# PIC18F2550-USB-HID-LC-Meter.net
KiCad netlist of a schematic drawn in EAGLE
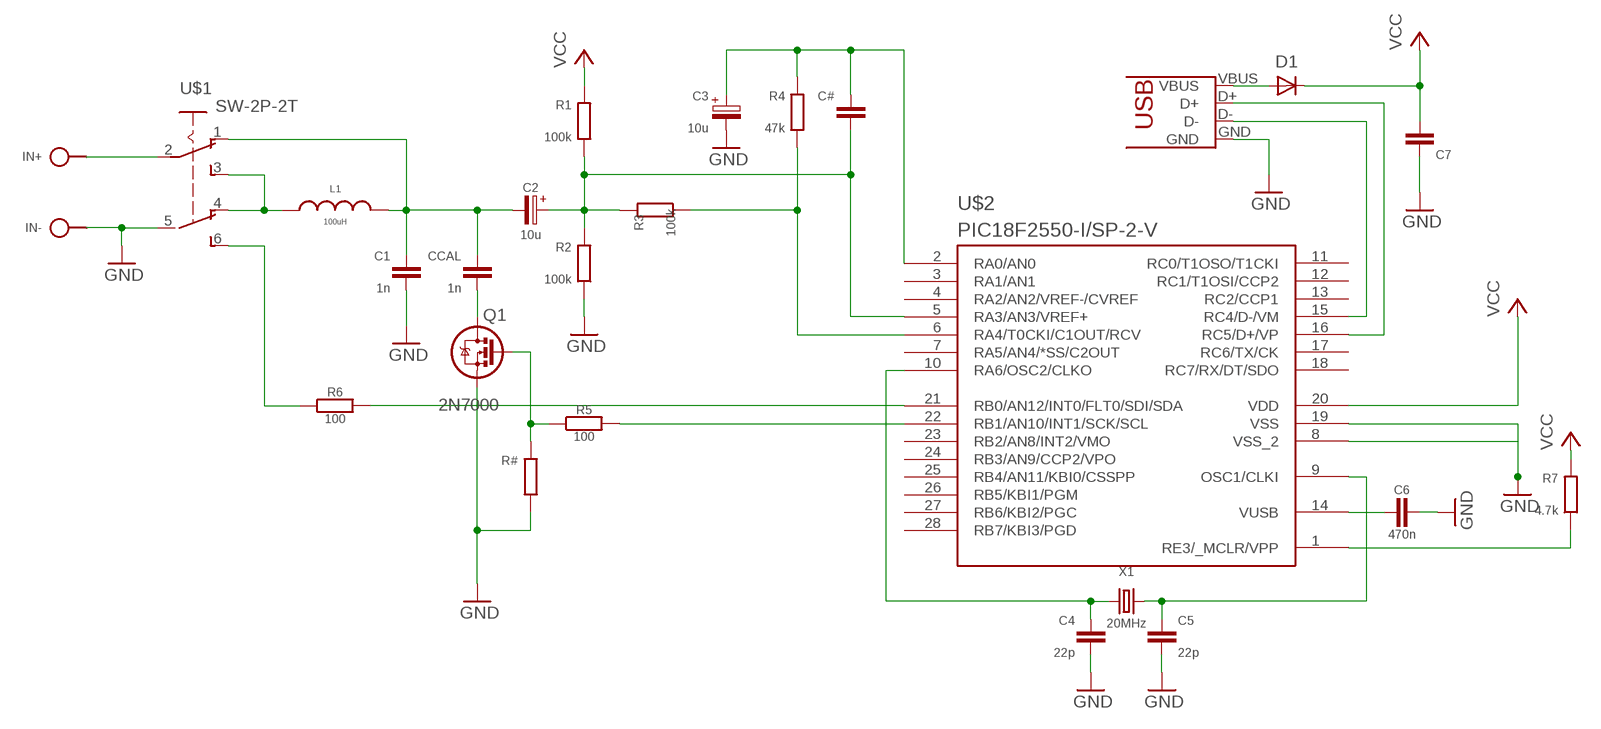
[diagram p0: schematic, sheet 1]

(export (version "E")
  (design (tool "Eeschema 10.0.6"))
  (components
    (comp (ref "C#")
      (value "C050-020X036")
      (footprint "eagle-import:C050-020X036")
      (libsource (lib "eagle-import") (part "C050-020X036"))
    )
    (comp (ref "C1")
      (value "1n")
      (footprint "eagle-import:C050-020X036")
      (libsource (lib "eagle-import") (part "C050-020X036"))
    )
    (comp (ref "C2")
      (value "10u")
      (footprint "eagle-import:E2.5-4_V")
      (libsource (lib "eagle-import") (part "CPOLE2,5-4/V"))
    )
    (comp (ref "C3")
      (value "10u")
      (footprint "eagle-import:E2,5-4")
      (libsource (lib "eagle-import") (part "CPOLE2,5-4"))
    )
    (comp (ref "C4")
      (value "22p")
      (footprint "eagle-import:C025-015X024_V")
      (libsource (lib "eagle-import") (part "C025-015X024"))
    )
    (comp (ref "C5")
      (value "22p")
      (footprint "eagle-import:C025-015X024_V")
      (libsource (lib "eagle-import") (part "C025-015X024"))
    )
    (comp (ref "C6")
      (value "470n")
      (footprint "eagle-import:C050-020X036")
      (libsource (lib "eagle-import") (part "C050-020X036"))
    )
    (comp (ref "C7")
      (value "C050-020X036")
      (footprint "eagle-import:C050-020X036")
      (libsource (lib "eagle-import") (part "C050-020X036"))
    )
    (comp (ref "CCAL")
      (value "1n")
      (footprint "eagle-import:C050-020X036")
      (libsource (lib "eagle-import") (part "C050-020X036"))
    )
    (comp (ref "D1")
      (value "1N414834-5")
      (footprint "eagle-import:DO34-5")
      (libsource (lib "eagle-import") (part "1N414834-5"))
    )
    (comp (ref "IN+")
      (value "SPAD")
      (footprint "eagle-import:SPAD")
      (libsource (lib "eagle-import") (part "SPAD"))
    )
    (comp (ref "IN-")
      (value "SPAD")
      (footprint "eagle-import:SPAD")
      (libsource (lib "eagle-import") (part "SPAD"))
    )
    (comp (ref "J1")
      (value "USB-PRINT")
      (footprint "eagle-import:USB-B-PRINT")
      (libsource (lib "eagle-import") (part "USB-PRINT"))
    )
    (comp (ref "L1")
      (value "100uH")
      (footprint "eagle-import:L-04_10-M")
      (libsource (lib "eagle-import") (part "L04/7-M"))
    )
    (comp (ref "Q1")
      (value "2N7000")
      (footprint "eagle-import:TO92")
      (libsource (lib "eagle-import") (part "2N7000"))
    )
    (comp (ref "R#")
      (value "R0202/7")
      (footprint "eagle-import:0202_7")
      (libsource (lib "eagle-import") (part "R0202/7"))
    )
    (comp (ref "R1")
      (value "100k")
      (footprint "eagle-import:0202_7")
      (libsource (lib "eagle-import") (part "R0202/7"))
    )
    (comp (ref "R2")
      (value "100k")
      (footprint "eagle-import:0202_7")
      (libsource (lib "eagle-import") (part "R0202/7"))
    )
    (comp (ref "R3")
      (value "100k")
      (footprint "eagle-import:0202_7")
      (libsource (lib "eagle-import") (part "R0202/7"))
    )
    (comp (ref "R4")
      (value "47k")
      (footprint "eagle-import:0202_7")
      (libsource (lib "eagle-import") (part "R0202/7"))
    )
    (comp (ref "R5")
      (value "100")
      (footprint "eagle-import:0202_7")
      (libsource (lib "eagle-import") (part "R0202/7"))
    )
    (comp (ref "R6")
      (value "100")
      (footprint "eagle-import:0202_7")
      (libsource (lib "eagle-import") (part "R0202/7"))
    )
    (comp (ref "R7")
      (value "4.7k")
      (footprint "eagle-import:0202_7")
      (libsource (lib "eagle-import") (part "R0202/7"))
    )
    (comp (ref "U$1")
      (value "SW-2P-2T")
      (footprint "eagle-import:SLSW-2P2T")
      (libsource (lib "eagle-import") (part "SW-2P-2T"))
    )
    (comp (ref "U$2")
      (value "PIC18F2550-I/SP-2-V")
      (footprint "eagle-import:DIL28-3_V")
      (libsource (lib "eagle-import") (part "PIC18F2550-I/SP-2-V"))
    )
    (comp (ref "X1")
      (value "20MHz")
      (footprint "eagle-import:HC49")
      (libsource (lib "eagle-import") (part "CRYSTALHC49"))
    )
  )
  (nets
    (net (code "1") (name "GND") (class "Default")
      (node (ref "C1") (pin "2") (pinfunction "2_2") (pintype "passive"))
      (node (ref "C3") (pin "-") (pinfunction "-_-") (pintype "passive"))
      (node (ref "C4") (pin "2") (pinfunction "2_2") (pintype "passive"))
      (node (ref "C5") (pin "2") (pinfunction "2_2") (pintype "passive"))
      (node (ref "C6") (pin "2") (pinfunction "2_2") (pintype "passive"))
      (node (ref "C7") (pin "1") (pinfunction "1_1") (pintype "passive"))
      (node (ref "IN-") (pin "1") (pinfunction "P$1_1") (pintype "bidirectional"))
      (node (ref "J1") (pin "GND") (pinfunction "GND_GND") (pintype "bidirectional"))
      (node (ref "Q1") (pin "1") (pinfunction "S_1") (pintype "passive"))
      (node (ref "R#") (pin "1") (pinfunction "1_1") (pintype "passive"))
      (node (ref "R2") (pin "1") (pinfunction "1_1") (pintype "passive"))
      (node (ref "U$1") (pin "5") (pinfunction "P1_5") (pintype "passive"))
      (node (ref "U$2") (pin "19") (pinfunction "VSS_19") (pintype "passive"))
      (node (ref "U$2") (pin "8") (pinfunction "VSS_2_8") (pintype "passive"))
    )
    (net (code "2") (name "Net-(D1-PadA)") (class "Default")
      (node (ref "D1") (pin "A") (pinfunction "A_A") (pintype "passive"))
      (node (ref "J1") (pin "VBUS") (pinfunction "VBUS_VBUS") (pintype "bidirectional"))
    )
    (net (code "3") (name "Net-(IN+-P$1)") (class "Default")
      (node (ref "IN+") (pin "1") (pinfunction "P$1_1") (pintype "bidirectional"))
      (node (ref "U$1") (pin "2") (pinfunction "P_2") (pintype "passive"))
    )
    (net (code "4") (name "Net-(Q1-D)") (class "Default")
      (node (ref "CCAL") (pin "2") (pinfunction "2_2") (pintype "passive"))
      (node (ref "Q1") (pin "3") (pinfunction "D_3") (pintype "passive"))
    )
    (net (code "5") (name "Net-(Q1-G)") (class "Default")
      (node (ref "Q1") (pin "2") (pinfunction "G_2") (pintype "passive"))
      (node (ref "R#") (pin "2") (pinfunction "2_2") (pintype "passive"))
      (node (ref "R5") (pin "1") (pinfunction "1_1") (pintype "passive"))
    )
    (net (code "6") (name "Net-(U$1-O)") (class "Default")
      (node (ref "C1") (pin "1") (pinfunction "1_1") (pintype "passive"))
      (node (ref "C2") (pin "-") (pinfunction "-_-") (pintype "passive"))
      (node (ref "CCAL") (pin "1") (pinfunction "1_1") (pintype "passive"))
      (node (ref "L1") (pin "2") (pinfunction "2_2") (pintype "passive"))
      (node (ref "U$1") (pin "1") (pinfunction "O_1") (pintype "passive"))
    )
    (net (code "7") (name "Net-(U$1-O1)") (class "Default")
      (node (ref "L1") (pin "1") (pinfunction "1_1") (pintype "passive"))
      (node (ref "U$1") (pin "3") (pinfunction "S_3") (pintype "passive"))
      (node (ref "U$1") (pin "4") (pinfunction "O1_4") (pintype "passive"))
    )
    (net (code "8") (name "Net-(U$1-S1)") (class "Default")
      (node (ref "R6") (pin "1") (pinfunction "1_1") (pintype "passive"))
      (node (ref "U$1") (pin "6") (pinfunction "S1_6") (pintype "passive"))
    )
    (net (code "9") (name "Net-(U$2-OSC1{slash}CLKI)") (class "Default")
      (node (ref "C5") (pin "1") (pinfunction "1_1") (pintype "passive"))
      (node (ref "U$2") (pin "9") (pinfunction "OSC1/CLKI_9") (pintype "passive"))
      (node (ref "X1") (pin "2") (pinfunction "2_2") (pintype "passive"))
    )
    (net (code "10") (name "Net-(U$2-RA0{slash}AN0)") (class "Default")
      (node (ref "C#") (pin "1") (pinfunction "1_1") (pintype "passive"))
      (node (ref "C3") (pin "+") (pinfunction "+_+") (pintype "passive"))
      (node (ref "R4") (pin "2") (pinfunction "2_2") (pintype "passive"))
      (node (ref "U$2") (pin "2") (pinfunction "RA0/AN0_2") (pintype "passive"))
    )
    (net (code "11") (name "Net-(U$2-RA3{slash}AN3{slash}VREF+)") (class "Default")
      (node (ref "C#") (pin "2") (pinfunction "2_2") (pintype "passive"))
      (node (ref "C2") (pin "+") (pinfunction "+_+") (pintype "passive"))
      (node (ref "R1") (pin "1") (pinfunction "1_1") (pintype "passive"))
      (node (ref "R2") (pin "2") (pinfunction "2_2") (pintype "passive"))
      (node (ref "R3") (pin "2") (pinfunction "2_2") (pintype "passive"))
      (node (ref "U$2") (pin "5") (pinfunction "RA3/AN3/VREF+_5") (pintype "passive"))
    )
    (net (code "12") (name "Net-(U$2-RA4{slash}T0CKI{slash}C1OUT{slash}RCV)") (class "Default")
      (node (ref "R3") (pin "1") (pinfunction "1_1") (pintype "passive"))
      (node (ref "R4") (pin "1") (pinfunction "1_1") (pintype "passive"))
      (node (ref "U$2") (pin "6") (pinfunction "RA4/T0CKI/C1OUT/RCV_6") (pintype "passive"))
    )
    (net (code "13") (name "Net-(U$2-RA6{slash}OSC2{slash}CLKO)") (class "Default")
      (node (ref "C4") (pin "1") (pinfunction "1_1") (pintype "passive"))
      (node (ref "U$2") (pin "10") (pinfunction "RA6/OSC2/CLKO_10") (pintype "passive"))
      (node (ref "X1") (pin "1") (pinfunction "1_1") (pintype "passive"))
    )
    (net (code "14") (name "Net-(U$2-RB0{slash}AN12{slash}INT0{slash}FLT0{slash}SDI{slash}SDA)") (class "Default")
      (node (ref "R6") (pin "2") (pinfunction "2_2") (pintype "passive"))
      (node (ref "U$2") (pin "21") (pinfunction "RB0/AN12/INT0/FLT0/SDI/SDA_21") (pintype "passive"))
    )
    (net (code "15") (name "Net-(U$2-RB1{slash}AN10{slash}INT1{slash}SCK{slash}SCL)") (class "Default")
      (node (ref "R5") (pin "2") (pinfunction "2_2") (pintype "passive"))
      (node (ref "U$2") (pin "22") (pinfunction "RB1/AN10/INT1/SCK/SCL_22") (pintype "passive"))
    )
    (net (code "16") (name "Net-(U$2-RC4{slash}D-{slash}VM)") (class "Default")
      (node (ref "J1") (pin "D-") (pinfunction "D-_D-") (pintype "bidirectional"))
      (node (ref "U$2") (pin "15") (pinfunction "RC4/D-/VM_15") (pintype "passive"))
    )
    (net (code "17") (name "Net-(U$2-RC5{slash}D+{slash}VP)") (class "Default")
      (node (ref "J1") (pin "D+") (pinfunction "D+_D+") (pintype "bidirectional"))
      (node (ref "U$2") (pin "16") (pinfunction "RC5/D+/VP_16") (pintype "passive"))
    )
    (net (code "18") (name "Net-(U$2-RE3{slash}_MCLR{slash}VPP)") (class "Default")
      (node (ref "R7") (pin "1") (pinfunction "1_1") (pintype "passive"))
      (node (ref "U$2") (pin "1") (pinfunction "RE3/_MCLR/VPP_1") (pintype "passive"))
    )
    (net (code "19") (name "Net-(U$2-VUSB)") (class "Default")
      (node (ref "C6") (pin "1") (pinfunction "1_1") (pintype "passive"))
      (node (ref "U$2") (pin "14") (pinfunction "VUSB_14") (pintype "passive"))
    )
    (net (code "20") (name "VCC") (class "Default")
      (node (ref "C7") (pin "2") (pinfunction "2_2") (pintype "passive"))
      (node (ref "D1") (pin "C") (pinfunction "C_C") (pintype "passive"))
      (node (ref "R1") (pin "2") (pinfunction "2_2") (pintype "passive"))
      (node (ref "R7") (pin "2") (pinfunction "2_2") (pintype "passive"))
      (node (ref "U$2") (pin "20") (pinfunction "VDD_20") (pintype "passive"))
    )
    (net (code "21") (name "unconnected-(U$2-RA1{slash}AN1-Pad3)") (class "Default")
      (node (ref "U$2") (pin "3") (pinfunction "RA1/AN1_3") (pintype "passive"))
    )
    (net (code "22") (name "unconnected-(U$2-RA2{slash}AN2{slash}VREF-{slash}CVREF-Pad4)") (class "Default")
      (node (ref "U$2") (pin "4") (pinfunction "RA2/AN2/VREF-/CVREF_4") (pintype "passive"))
    )
    (net (code "23") (name "unconnected-(U$2-RA5{slash}AN4{slash}*SS{slash}C2OUT-Pad7)") (class "Default")
      (node (ref "U$2") (pin "7") (pinfunction "RA5/AN4/*SS/C2OUT_7") (pintype "passive"))
    )
    (net (code "24") (name "unconnected-(U$2-RB2{slash}AN8{slash}INT2{slash}VMO-Pad23)") (class "Default")
      (node (ref "U$2") (pin "23") (pinfunction "RB2/AN8/INT2/VMO_23") (pintype "passive"))
    )
    (net (code "25") (name "unconnected-(U$2-RB3{slash}AN9{slash}CCP2{slash}VPO-Pad24)") (class "Default")
      (node (ref "U$2") (pin "24") (pinfunction "RB3/AN9/CCP2/VPO_24") (pintype "passive"))
    )
    (net (code "26") (name "unconnected-(U$2-RB4{slash}AN11{slash}KBI0{slash}CSSPP-Pad25)") (class "Default")
      (node (ref "U$2") (pin "25") (pinfunction "RB4/AN11/KBI0/CSSPP_25") (pintype "passive"))
    )
    (net (code "27") (name "unconnected-(U$2-RB5{slash}KBI1{slash}PGM-Pad26)") (class "Default")
      (node (ref "U$2") (pin "26") (pinfunction "RB5/KBI1/PGM_26") (pintype "passive"))
    )
    (net (code "28") (name "unconnected-(U$2-RB6{slash}KBI2{slash}PGC-Pad27)") (class "Default")
      (node (ref "U$2") (pin "27") (pinfunction "RB6/KBI2/PGC_27") (pintype "passive"))
    )
    (net (code "29") (name "unconnected-(U$2-RB7{slash}KBI3{slash}PGD-Pad28)") (class "Default")
      (node (ref "U$2") (pin "28") (pinfunction "RB7/KBI3/PGD_28") (pintype "passive"))
    )
    (net (code "30") (name "unconnected-(U$2-RC0{slash}T1OSO{slash}T1CKI-Pad11)") (class "Default")
      (node (ref "U$2") (pin "11") (pinfunction "RC0/T1OSO/T1CKI_11") (pintype "passive"))
    )
    (net (code "31") (name "unconnected-(U$2-RC1{slash}T1OSI{slash}CCP2-Pad12)") (class "Default")
      (node (ref "U$2") (pin "12") (pinfunction "RC1/T1OSI/CCP2_12") (pintype "passive"))
    )
    (net (code "32") (name "unconnected-(U$2-RC2{slash}CCP1-Pad13)") (class "Default")
      (node (ref "U$2") (pin "13") (pinfunction "RC2/CCP1_13") (pintype "passive"))
    )
    (net (code "33") (name "unconnected-(U$2-RC6{slash}TX{slash}CK-Pad17)") (class "Default")
      (node (ref "U$2") (pin "17") (pinfunction "RC6/TX/CK_17") (pintype "passive"))
    )
    (net (code "34") (name "unconnected-(U$2-RC7{slash}RX{slash}DT{slash}SDO-Pad18)") (class "Default")
      (node (ref "U$2") (pin "18") (pinfunction "RC7/RX/DT/SDO_18") (pintype "passive"))
    )
  )
)
